# sensors.net
KiCad netlist of a schematic drawn in EAGLE
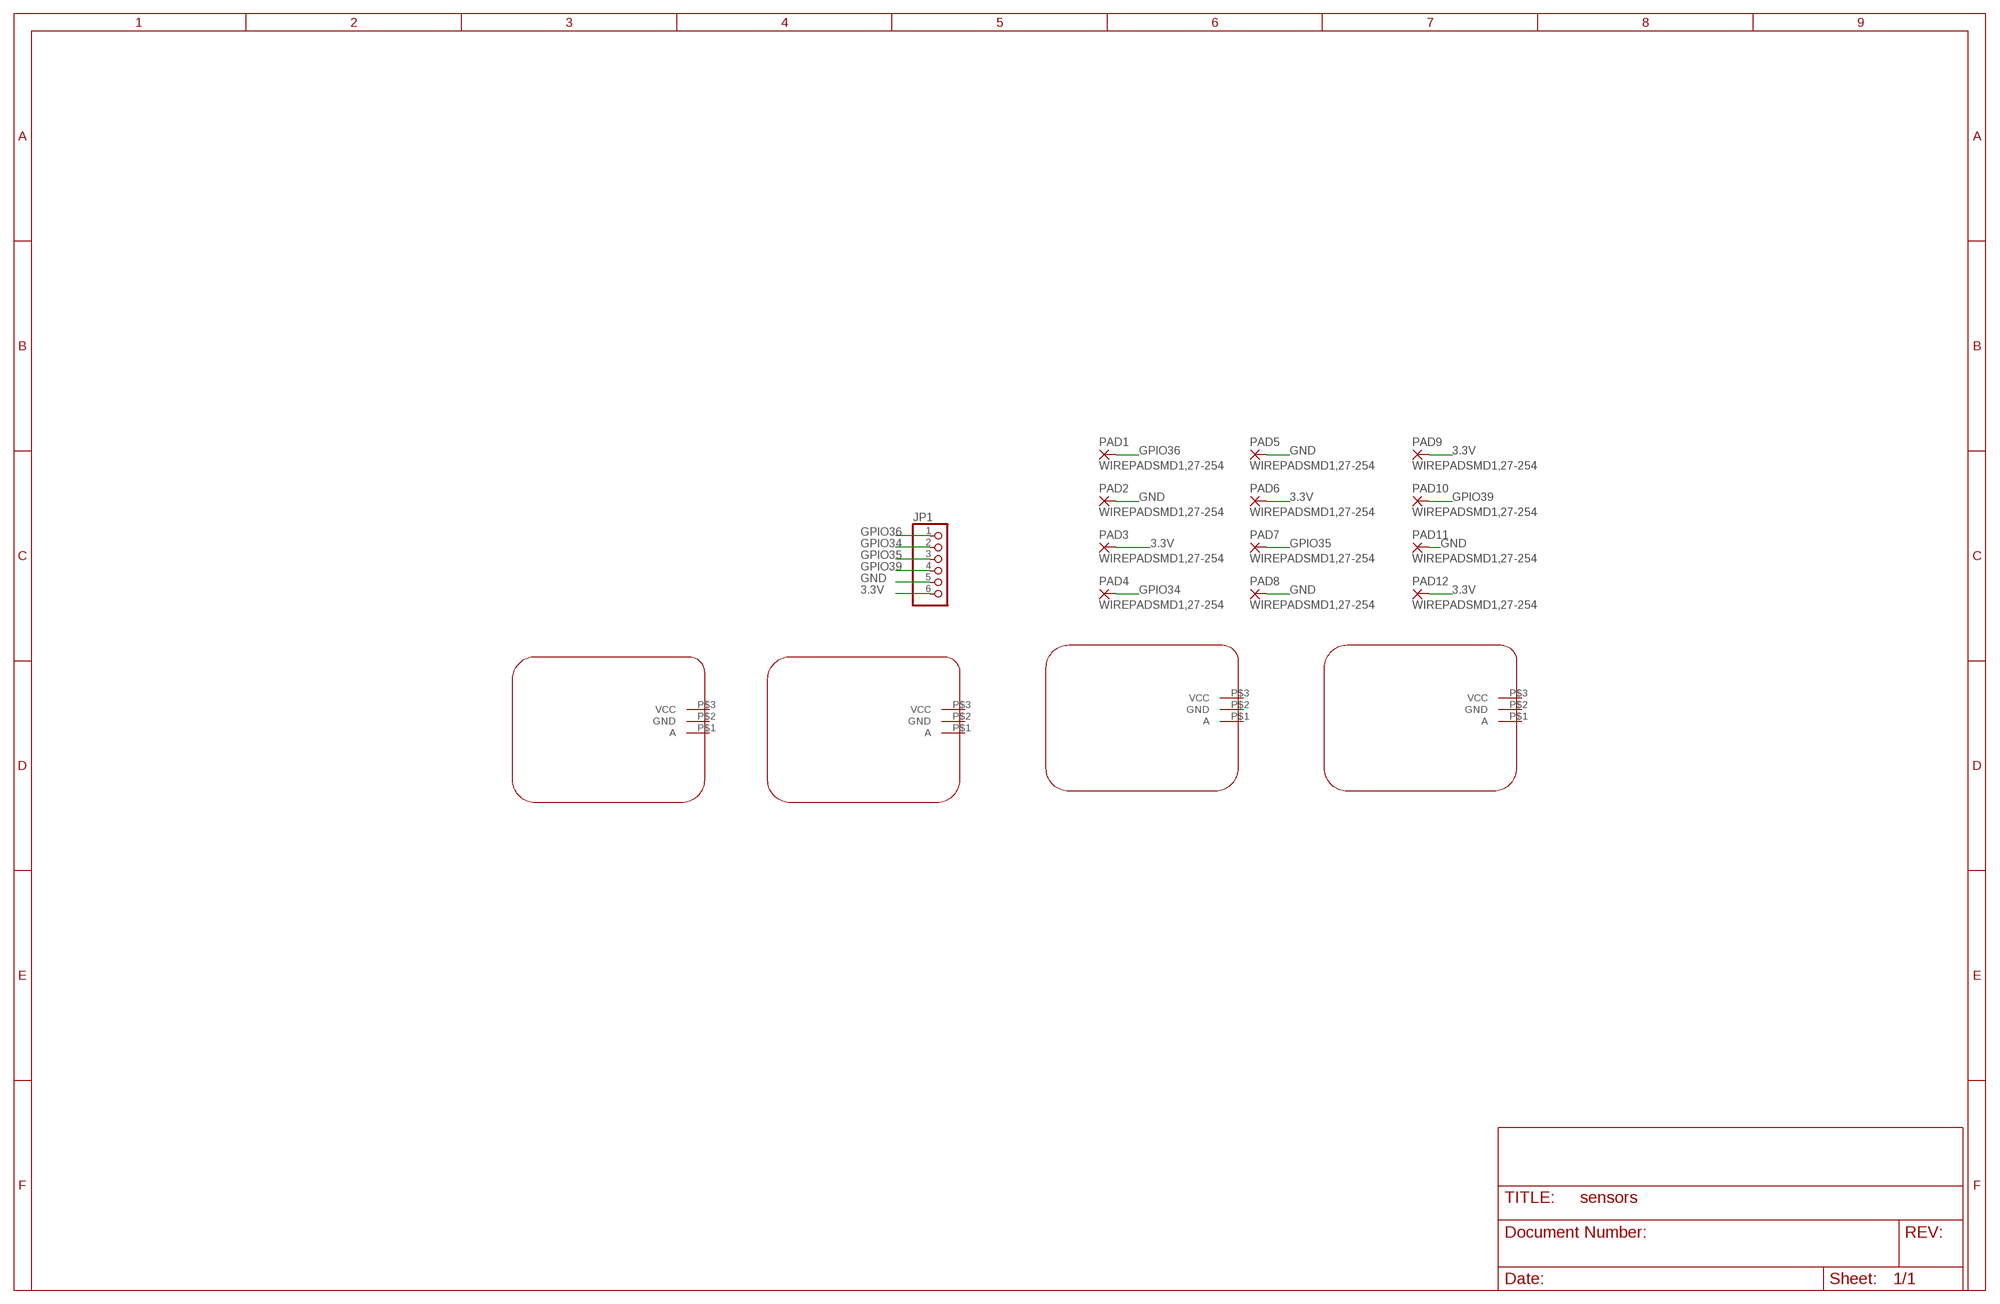
[diagram p0: schematic, sheet 1]

(export (version "E")
  (design (tool "Eeschema 10.0.6"))
  (components
    (comp (ref "JP1")
      (value "PINHD-1X6")
      (footprint "eagle-import:1X06")
      (libsource (lib "eagle-import") (part "PINHD-1X6"))
    )
    (comp (ref "PAD1")
      (value "WIREPADSMD1,27-254")
      (footprint "eagle-import:SMD1,27-2,54")
      (libsource (lib "eagle-import") (part "WIREPADSMD1,27-254"))
    )
    (comp (ref "PAD2")
      (value "WIREPADSMD1,27-254")
      (footprint "eagle-import:SMD1,27-2,54")
      (libsource (lib "eagle-import") (part "WIREPADSMD1,27-254"))
    )
    (comp (ref "PAD3")
      (value "WIREPADSMD1,27-254")
      (footprint "eagle-import:SMD1,27-2,54")
      (libsource (lib "eagle-import") (part "WIREPADSMD1,27-254"))
    )
    (comp (ref "PAD4")
      (value "WIREPADSMD1,27-254")
      (footprint "eagle-import:SMD1,27-2,54")
      (libsource (lib "eagle-import") (part "WIREPADSMD1,27-254"))
    )
    (comp (ref "PAD5")
      (value "WIREPADSMD1,27-254")
      (footprint "eagle-import:SMD1,27-2,54")
      (libsource (lib "eagle-import") (part "WIREPADSMD1,27-254"))
    )
    (comp (ref "PAD6")
      (value "WIREPADSMD1,27-254")
      (footprint "eagle-import:SMD1,27-2,54")
      (libsource (lib "eagle-import") (part "WIREPADSMD1,27-254"))
    )
    (comp (ref "PAD7")
      (value "WIREPADSMD1,27-254")
      (footprint "eagle-import:SMD1,27-2,54")
      (libsource (lib "eagle-import") (part "WIREPADSMD1,27-254"))
    )
    (comp (ref "PAD8")
      (value "WIREPADSMD1,27-254")
      (footprint "eagle-import:SMD1,27-2,54")
      (libsource (lib "eagle-import") (part "WIREPADSMD1,27-254"))
    )
    (comp (ref "PAD9")
      (value "WIREPADSMD1,27-254")
      (footprint "eagle-import:SMD1,27-2,54")
      (libsource (lib "eagle-import") (part "WIREPADSMD1,27-254"))
    )
    (comp (ref "PAD10")
      (value "WIREPADSMD1,27-254")
      (footprint "eagle-import:SMD1,27-2,54")
      (libsource (lib "eagle-import") (part "WIREPADSMD1,27-254"))
    )
    (comp (ref "PAD11")
      (value "WIREPADSMD1,27-254")
      (footprint "eagle-import:SMD1,27-2,54")
      (libsource (lib "eagle-import") (part "WIREPADSMD1,27-254"))
    )
    (comp (ref "PAD12")
      (value "WIREPADSMD1,27-254")
      (footprint "eagle-import:SMD1,27-2,54")
      (libsource (lib "eagle-import") (part "WIREPADSMD1,27-254"))
    )
    (comp (ref "U$1")
      (value "SEN0244")
      (footprint "eagle-import:PACKAGE")
      (libsource (lib "eagle-import") (part "SEN0244"))
    )
    (comp (ref "U$2")
      (value "SEN0244")
      (footprint "eagle-import:PACKAGE")
      (libsource (lib "eagle-import") (part "SEN0244"))
    )
    (comp (ref "U$3")
      (value "SEN0244")
      (footprint "eagle-import:PACKAGE")
      (libsource (lib "eagle-import") (part "SEN0244"))
    )
    (comp (ref "U$4")
      (value "SEN0244")
      (footprint "eagle-import:PACKAGE")
      (libsource (lib "eagle-import") (part "SEN0244"))
    )
  )
  (nets
    (net (code "1") (name "/3.3V") (class "Default")
      (node (ref "JP1") (pin "6") (pinfunction "6_6") (pintype "passive"))
      (node (ref "PAD12") (pin "1") (pinfunction "P_1") (pintype "passive"))
      (node (ref "PAD3") (pin "1") (pinfunction "P_1") (pintype "passive"))
      (node (ref "PAD6") (pin "1") (pinfunction "P_1") (pintype "passive"))
      (node (ref "PAD9") (pin "1") (pinfunction "P_1") (pintype "passive"))
    )
    (net (code "2") (name "/GND") (class "Default")
      (node (ref "JP1") (pin "5") (pinfunction "5_5") (pintype "passive"))
      (node (ref "PAD11") (pin "1") (pinfunction "P_1") (pintype "passive"))
      (node (ref "PAD2") (pin "1") (pinfunction "P_1") (pintype "passive"))
      (node (ref "PAD5") (pin "1") (pinfunction "P_1") (pintype "passive"))
      (node (ref "PAD8") (pin "1") (pinfunction "P_1") (pintype "passive"))
    )
    (net (code "3") (name "/GPIO34") (class "Default")
      (node (ref "JP1") (pin "2") (pinfunction "2_2") (pintype "passive"))
      (node (ref "PAD4") (pin "1") (pinfunction "P_1") (pintype "passive"))
    )
    (net (code "4") (name "/GPIO35") (class "Default")
      (node (ref "JP1") (pin "3") (pinfunction "3_3") (pintype "passive"))
      (node (ref "PAD7") (pin "1") (pinfunction "P_1") (pintype "passive"))
    )
    (net (code "5") (name "/GPIO36") (class "Default")
      (node (ref "JP1") (pin "1") (pinfunction "1_1") (pintype "passive"))
      (node (ref "PAD1") (pin "1") (pinfunction "P_1") (pintype "passive"))
    )
    (net (code "6") (name "/GPIO39") (class "Default")
      (node (ref "JP1") (pin "4") (pinfunction "4_4") (pintype "passive"))
      (node (ref "PAD10") (pin "1") (pinfunction "P_1") (pintype "passive"))
    )
    (net (code "7") (name "unconnected-(U$1-A-PadP$1)") (class "Default")
      (node (ref "U$1") (pin "P$1") (pinfunction "A_P$1") (pintype "bidirectional"))
    )
    (net (code "8") (name "unconnected-(U$1-GND-PadP$2)") (class "Default")
      (node (ref "U$1") (pin "P$2") (pinfunction "GND_P$2") (pintype "bidirectional"))
    )
    (net (code "9") (name "unconnected-(U$1-VCC-PadP$3)") (class "Default")
      (node (ref "U$1") (pin "P$3") (pinfunction "VCC_P$3") (pintype "bidirectional"))
    )
    (net (code "10") (name "unconnected-(U$2-A-PadP$1)") (class "Default")
      (node (ref "U$2") (pin "P$1") (pinfunction "A_P$1") (pintype "bidirectional"))
    )
    (net (code "11") (name "unconnected-(U$2-GND-PadP$2)") (class "Default")
      (node (ref "U$2") (pin "P$2") (pinfunction "GND_P$2") (pintype "bidirectional"))
    )
    (net (code "12") (name "unconnected-(U$2-VCC-PadP$3)") (class "Default")
      (node (ref "U$2") (pin "P$3") (pinfunction "VCC_P$3") (pintype "bidirectional"))
    )
    (net (code "13") (name "unconnected-(U$3-A-PadP$1)") (class "Default")
      (node (ref "U$3") (pin "P$1") (pinfunction "A_P$1") (pintype "bidirectional"))
    )
    (net (code "14") (name "unconnected-(U$3-GND-PadP$2)") (class "Default")
      (node (ref "U$3") (pin "P$2") (pinfunction "GND_P$2") (pintype "bidirectional"))
    )
    (net (code "15") (name "unconnected-(U$3-VCC-PadP$3)") (class "Default")
      (node (ref "U$3") (pin "P$3") (pinfunction "VCC_P$3") (pintype "bidirectional"))
    )
    (net (code "16") (name "unconnected-(U$4-A-PadP$1)") (class "Default")
      (node (ref "U$4") (pin "P$1") (pinfunction "A_P$1") (pintype "bidirectional"))
    )
    (net (code "17") (name "unconnected-(U$4-GND-PadP$2)") (class "Default")
      (node (ref "U$4") (pin "P$2") (pinfunction "GND_P$2") (pintype "bidirectional"))
    )
    (net (code "18") (name "unconnected-(U$4-VCC-PadP$3)") (class "Default")
      (node (ref "U$4") (pin "P$3") (pinfunction "VCC_P$3") (pintype "bidirectional"))
    )
  )
)
